# sensor-hub-lr.net
KiCad netlist of a schematic drawn in EAGLE
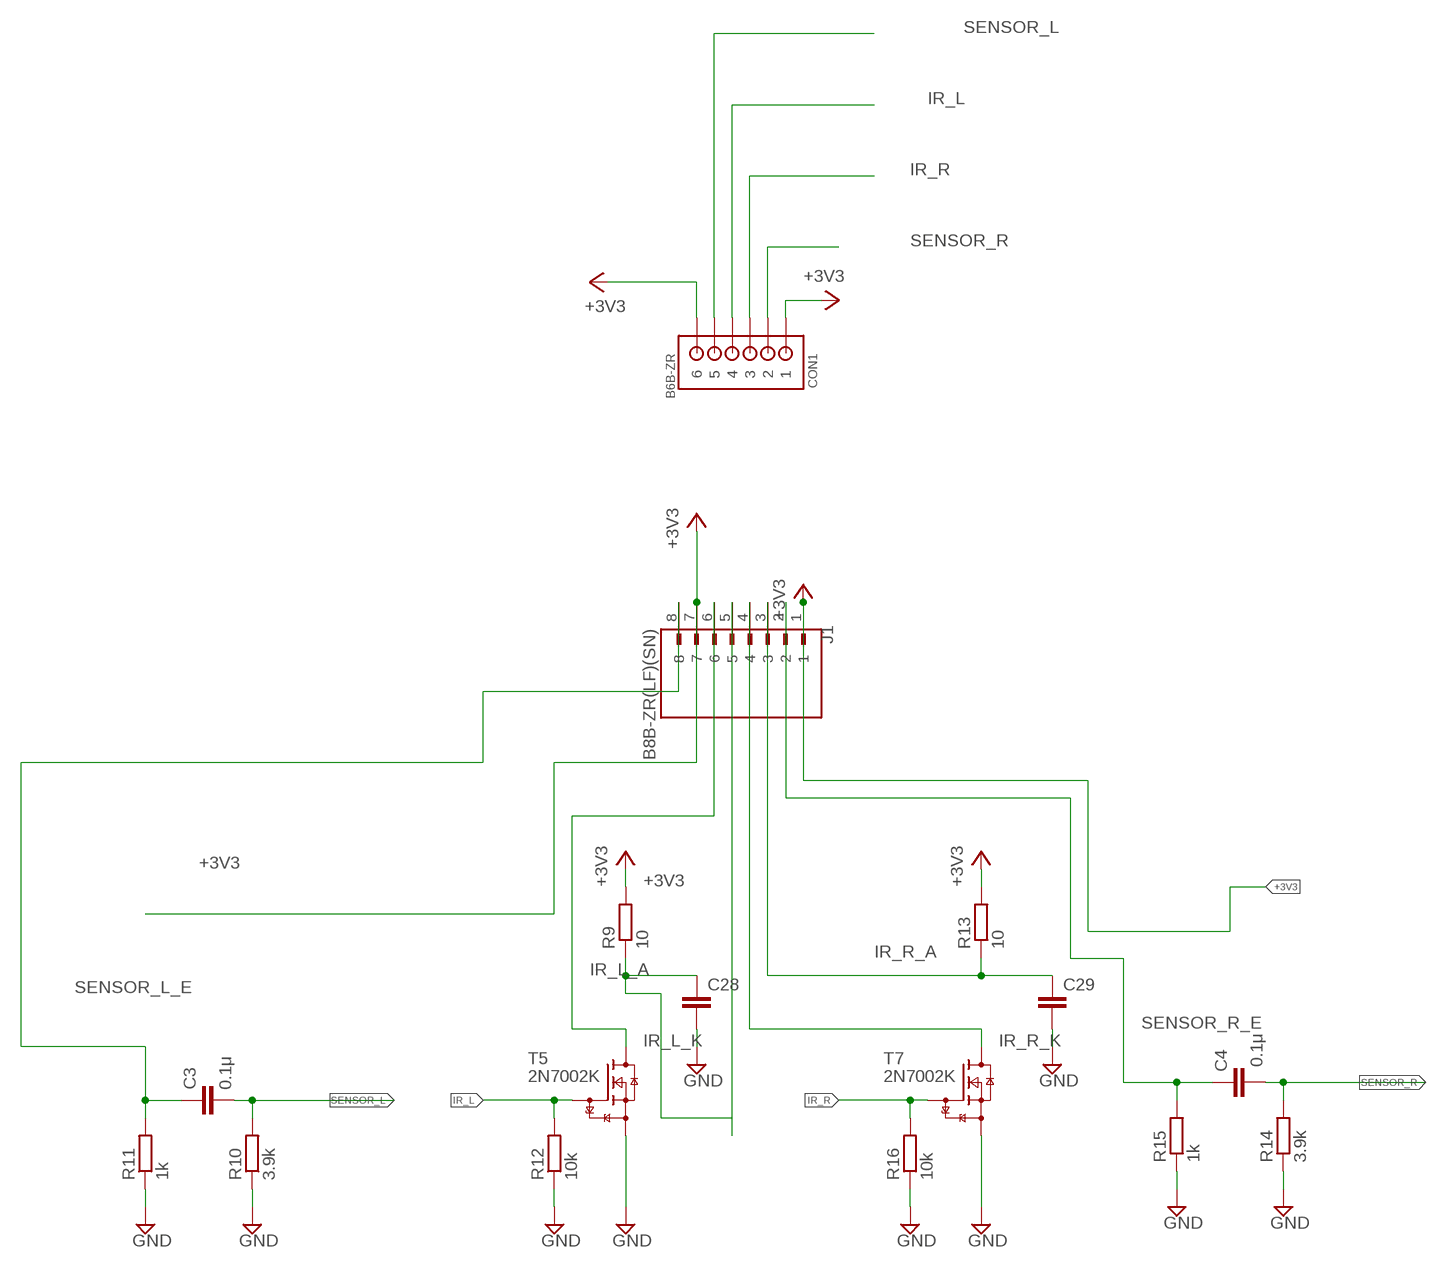
[diagram p0: schematic, sheet 1]

(export (version "E")
  (design (tool "Eeschema 10.0.6"))
  (components
    (comp (ref "C3")
      (value "0.1μ")
      (footprint "eagle-import:C0603")
      (libsource (lib "eagle-import") (part "C-EUC0603"))
    )
    (comp (ref "C4")
      (value "0.1μ")
      (footprint "eagle-import:C0603")
      (libsource (lib "eagle-import") (part "C-EUC0603"))
    )
    (comp (ref "C28")
      (value "C-EUC1206")
      (footprint "eagle-import:C1206")
      (libsource (lib "eagle-import") (part "C-EUC1206"))
    )
    (comp (ref "C29")
      (value "C-EUC1206")
      (footprint "eagle-import:C1206")
      (libsource (lib "eagle-import") (part "C-EUC1206"))
    )
    (comp (ref "CON1")
      (value "B6B-ZR")
      (footprint "eagle-import:B6B-ZR")
      (libsource (lib "eagle-import") (part "B6B-ZR"))
    )
    (comp (ref "J1")
      (value "B8B-ZR(LF)(SN)")
      (footprint "eagle-import:JST_B8B-ZR(LF)(SN)")
      (fields (field (name "MF") "JST") (field (name "MP") "B8B-ZR (LF)(SN)"))
      (libsource (lib "eagle-import") (part "B8B-ZR(LF)(SN)"))
    )
    (comp (ref "R9")
      (value "10")
      (footprint "eagle-import:R0603")
      (libsource (lib "eagle-import") (part "R-EU_R0603"))
    )
    (comp (ref "R10")
      (value "3.9k")
      (footprint "eagle-import:R0603")
      (libsource (lib "eagle-import") (part "R-EU_R0603"))
    )
    (comp (ref "R11")
      (value "1k")
      (footprint "eagle-import:R0603")
      (libsource (lib "eagle-import") (part "R-EU_R0603"))
    )
    (comp (ref "R12")
      (value "10k")
      (footprint "eagle-import:R0603")
      (libsource (lib "eagle-import") (part "R-EU_R0603"))
    )
    (comp (ref "R13")
      (value "10")
      (footprint "eagle-import:R0603")
      (libsource (lib "eagle-import") (part "R-EU_R0603"))
    )
    (comp (ref "R14")
      (value "3.9k")
      (footprint "eagle-import:R0603")
      (libsource (lib "eagle-import") (part "R-EU_R0603"))
    )
    (comp (ref "R15")
      (value "1k")
      (footprint "eagle-import:R0603")
      (libsource (lib "eagle-import") (part "R-EU_R0603"))
    )
    (comp (ref "R16")
      (value "10k")
      (footprint "eagle-import:R0603")
      (libsource (lib "eagle-import") (part "R-EU_R0603"))
    )
    (comp (ref "T5")
      (value "2N7002K")
      (footprint "eagle-import:SOT23")
      (libsource (lib "eagle-import") (part "2N7002K"))
    )
    (comp (ref "T7")
      (value "2N7002K")
      (footprint "eagle-import:SOT23")
      (libsource (lib "eagle-import") (part "2N7002K"))
    )
  )
  (nets
    (net (code "1") (name "+3V3") (class "Default")
      (node (ref "CON1") (pin "1") (pinfunction "1_1") (pintype "bidirectional"))
      (node (ref "CON1") (pin "6") (pinfunction "6_6") (pintype "bidirectional"))
      (node (ref "J1") (pin "1") (pinfunction "1_1") (pintype "passive"))
      (node (ref "J1") (pin "7") (pinfunction "7_7") (pintype "passive"))
      (node (ref "R13") (pin "2") (pinfunction "2_2") (pintype "passive"))
      (node (ref "R9") (pin "2") (pinfunction "2_2") (pintype "passive"))
    )
    (net (code "2") (name "/IR_L_A") (class "Default")
      (node (ref "C28") (pin "1") (pinfunction "1_1") (pintype "passive"))
      (node (ref "J1") (pin "5") (pinfunction "5_5") (pintype "passive"))
      (node (ref "R9") (pin "1") (pinfunction "1_1") (pintype "passive"))
    )
    (net (code "3") (name "/IR_L_K") (class "Default")
      (node (ref "J1") (pin "6") (pinfunction "6_6") (pintype "passive"))
      (node (ref "T5") (pin "3") (pinfunction "D_3") (pintype "passive"))
    )
    (net (code "4") (name "/IR_R_A") (class "Default")
      (node (ref "C29") (pin "1") (pinfunction "1_1") (pintype "passive"))
      (node (ref "J1") (pin "3") (pinfunction "3_3") (pintype "passive"))
      (node (ref "R13") (pin "1") (pinfunction "1_1") (pintype "passive"))
    )
    (net (code "5") (name "/IR_R_K") (class "Default")
      (node (ref "J1") (pin "4") (pinfunction "4_4") (pintype "passive"))
      (node (ref "T7") (pin "3") (pinfunction "D_3") (pintype "passive"))
    )
    (net (code "6") (name "/SENSOR_L_E") (class "Default")
      (node (ref "C3") (pin "1") (pinfunction "1_1") (pintype "passive"))
      (node (ref "J1") (pin "8") (pinfunction "8_8") (pintype "passive"))
      (node (ref "R11") (pin "2") (pinfunction "2_2") (pintype "passive"))
    )
    (net (code "7") (name "/SENSOR_R_E") (class "Default")
      (node (ref "C4") (pin "1") (pinfunction "1_1") (pintype "passive"))
      (node (ref "J1") (pin "2") (pinfunction "2_2") (pintype "passive"))
      (node (ref "R15") (pin "2") (pinfunction "2_2") (pintype "passive"))
    )
    (net (code "8") (name "GND") (class "Default")
      (node (ref "C28") (pin "2") (pinfunction "2_2") (pintype "passive"))
      (node (ref "C29") (pin "2") (pinfunction "2_2") (pintype "passive"))
      (node (ref "R10") (pin "1") (pinfunction "1_1") (pintype "passive"))
      (node (ref "R11") (pin "1") (pinfunction "1_1") (pintype "passive"))
      (node (ref "R12") (pin "1") (pinfunction "1_1") (pintype "passive"))
      (node (ref "R14") (pin "1") (pinfunction "1_1") (pintype "passive"))
      (node (ref "R15") (pin "1") (pinfunction "1_1") (pintype "passive"))
      (node (ref "R16") (pin "1") (pinfunction "1_1") (pintype "passive"))
      (node (ref "T5") (pin "2") (pinfunction "S_2") (pintype "passive"))
      (node (ref "T7") (pin "2") (pinfunction "S_2") (pintype "passive"))
    )
    (net (code "9") (name "IR_L") (class "Default")
      (node (ref "CON1") (pin "4") (pinfunction "4_4") (pintype "bidirectional"))
      (node (ref "R12") (pin "2") (pinfunction "2_2") (pintype "passive"))
      (node (ref "T5") (pin "1") (pinfunction "G_1") (pintype "passive"))
    )
    (net (code "10") (name "IR_R") (class "Default")
      (node (ref "CON1") (pin "3") (pinfunction "3_3") (pintype "bidirectional"))
      (node (ref "R16") (pin "2") (pinfunction "2_2") (pintype "passive"))
      (node (ref "T7") (pin "1") (pinfunction "G_1") (pintype "passive"))
    )
    (net (code "11") (name "SENSOR_L") (class "Default")
      (node (ref "C3") (pin "2") (pinfunction "2_2") (pintype "passive"))
      (node (ref "CON1") (pin "5") (pinfunction "5_5") (pintype "bidirectional"))
      (node (ref "R10") (pin "2") (pinfunction "2_2") (pintype "passive"))
    )
    (net (code "12") (name "SENSOR_R") (class "Default")
      (node (ref "C4") (pin "2") (pinfunction "2_2") (pintype "passive"))
      (node (ref "CON1") (pin "2") (pinfunction "2_2") (pintype "bidirectional"))
      (node (ref "R14") (pin "2") (pinfunction "2_2") (pintype "passive"))
    )
  )
)
